# hybrid.net
KiCad netlist of a schematic drawn in EAGLE
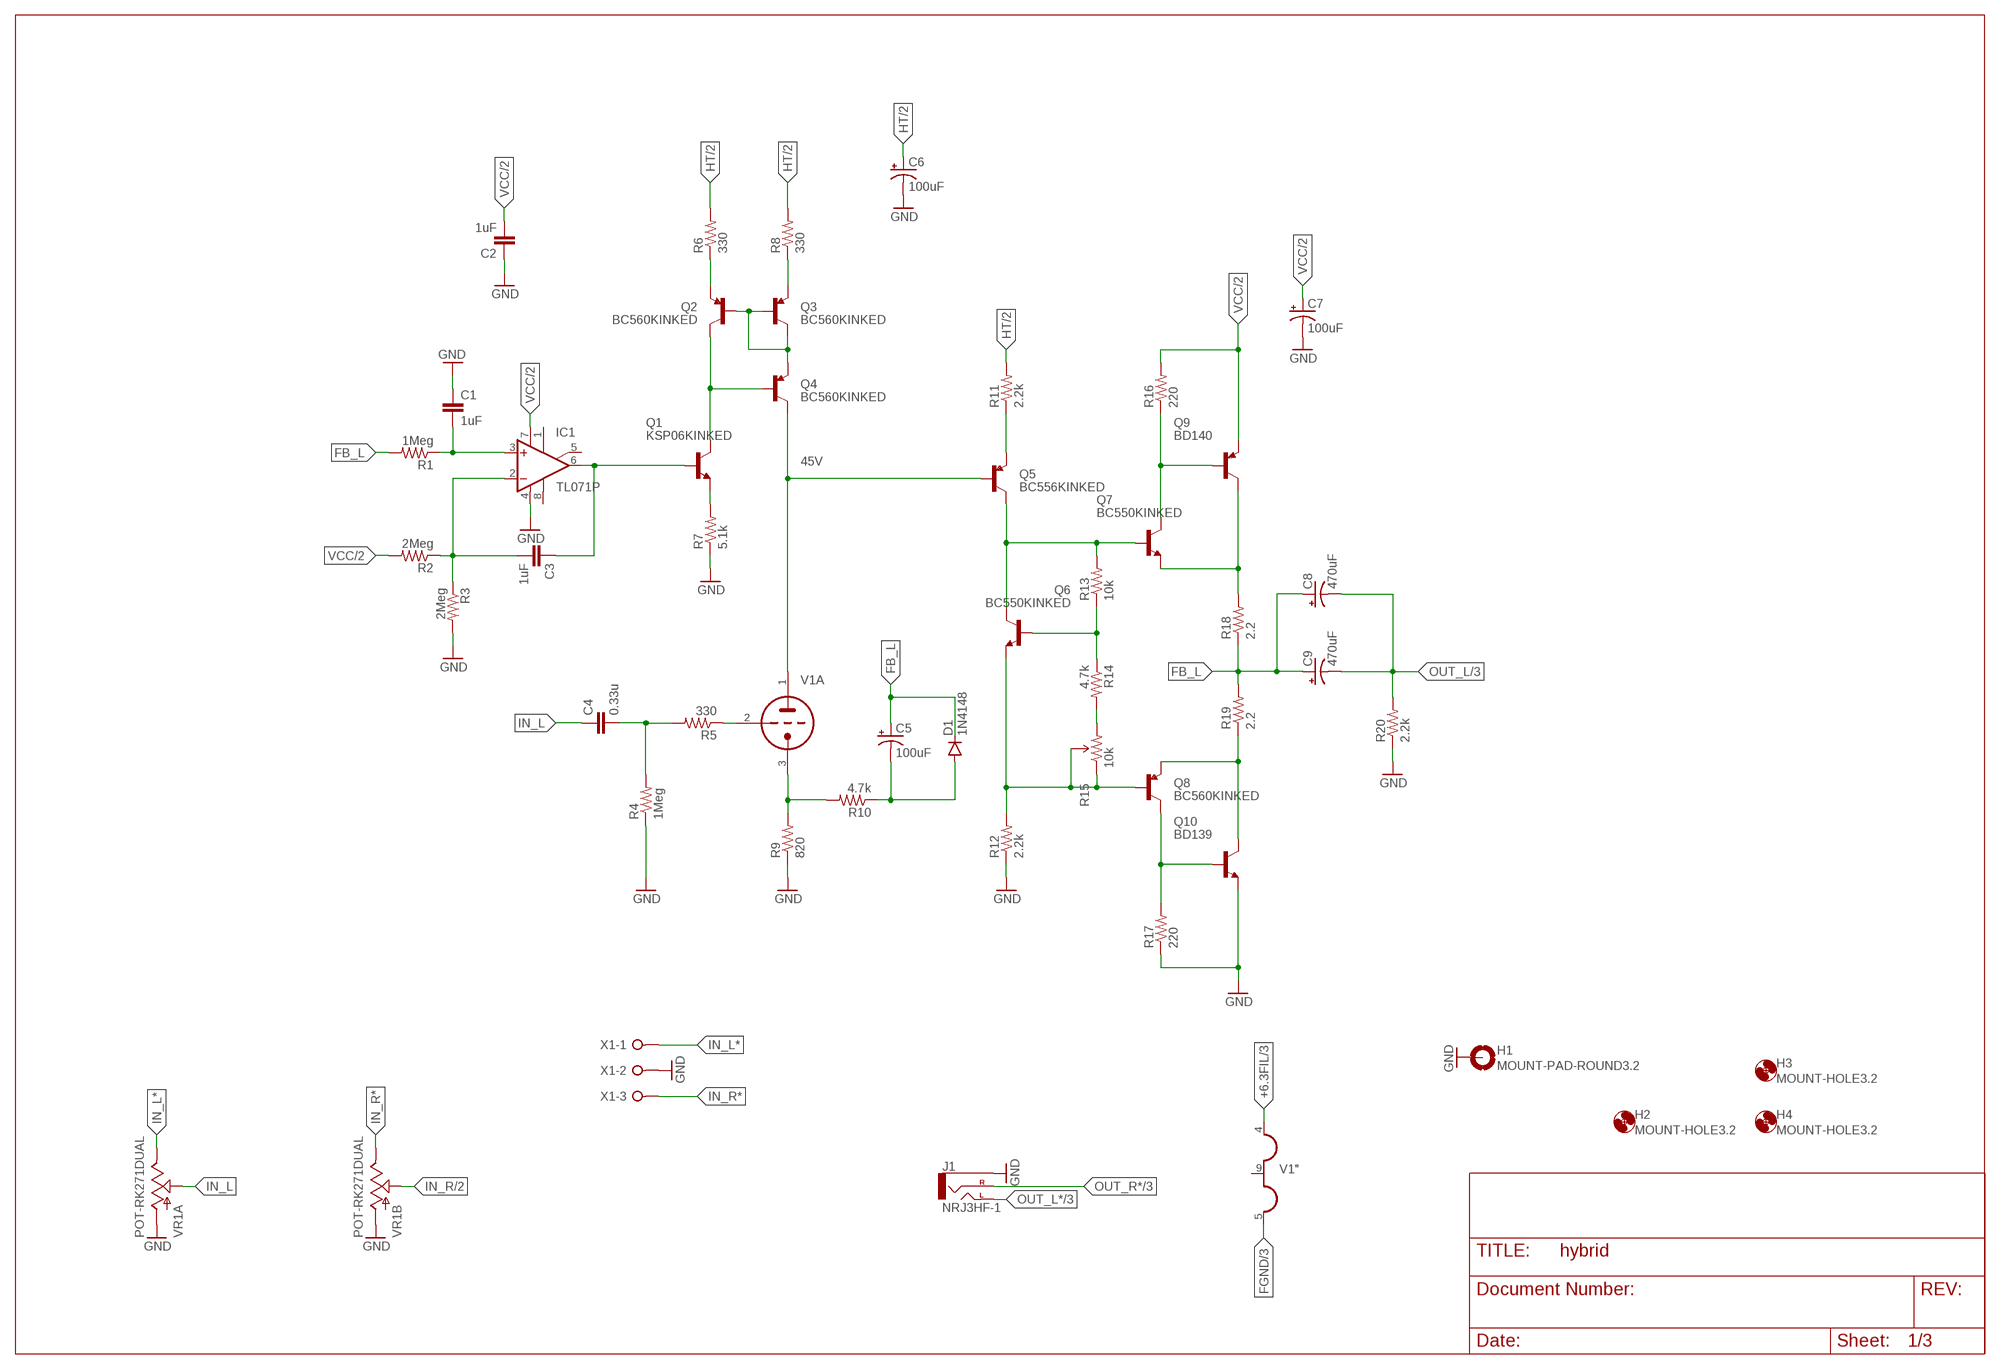
[diagram p0: schematic, sheet 1]
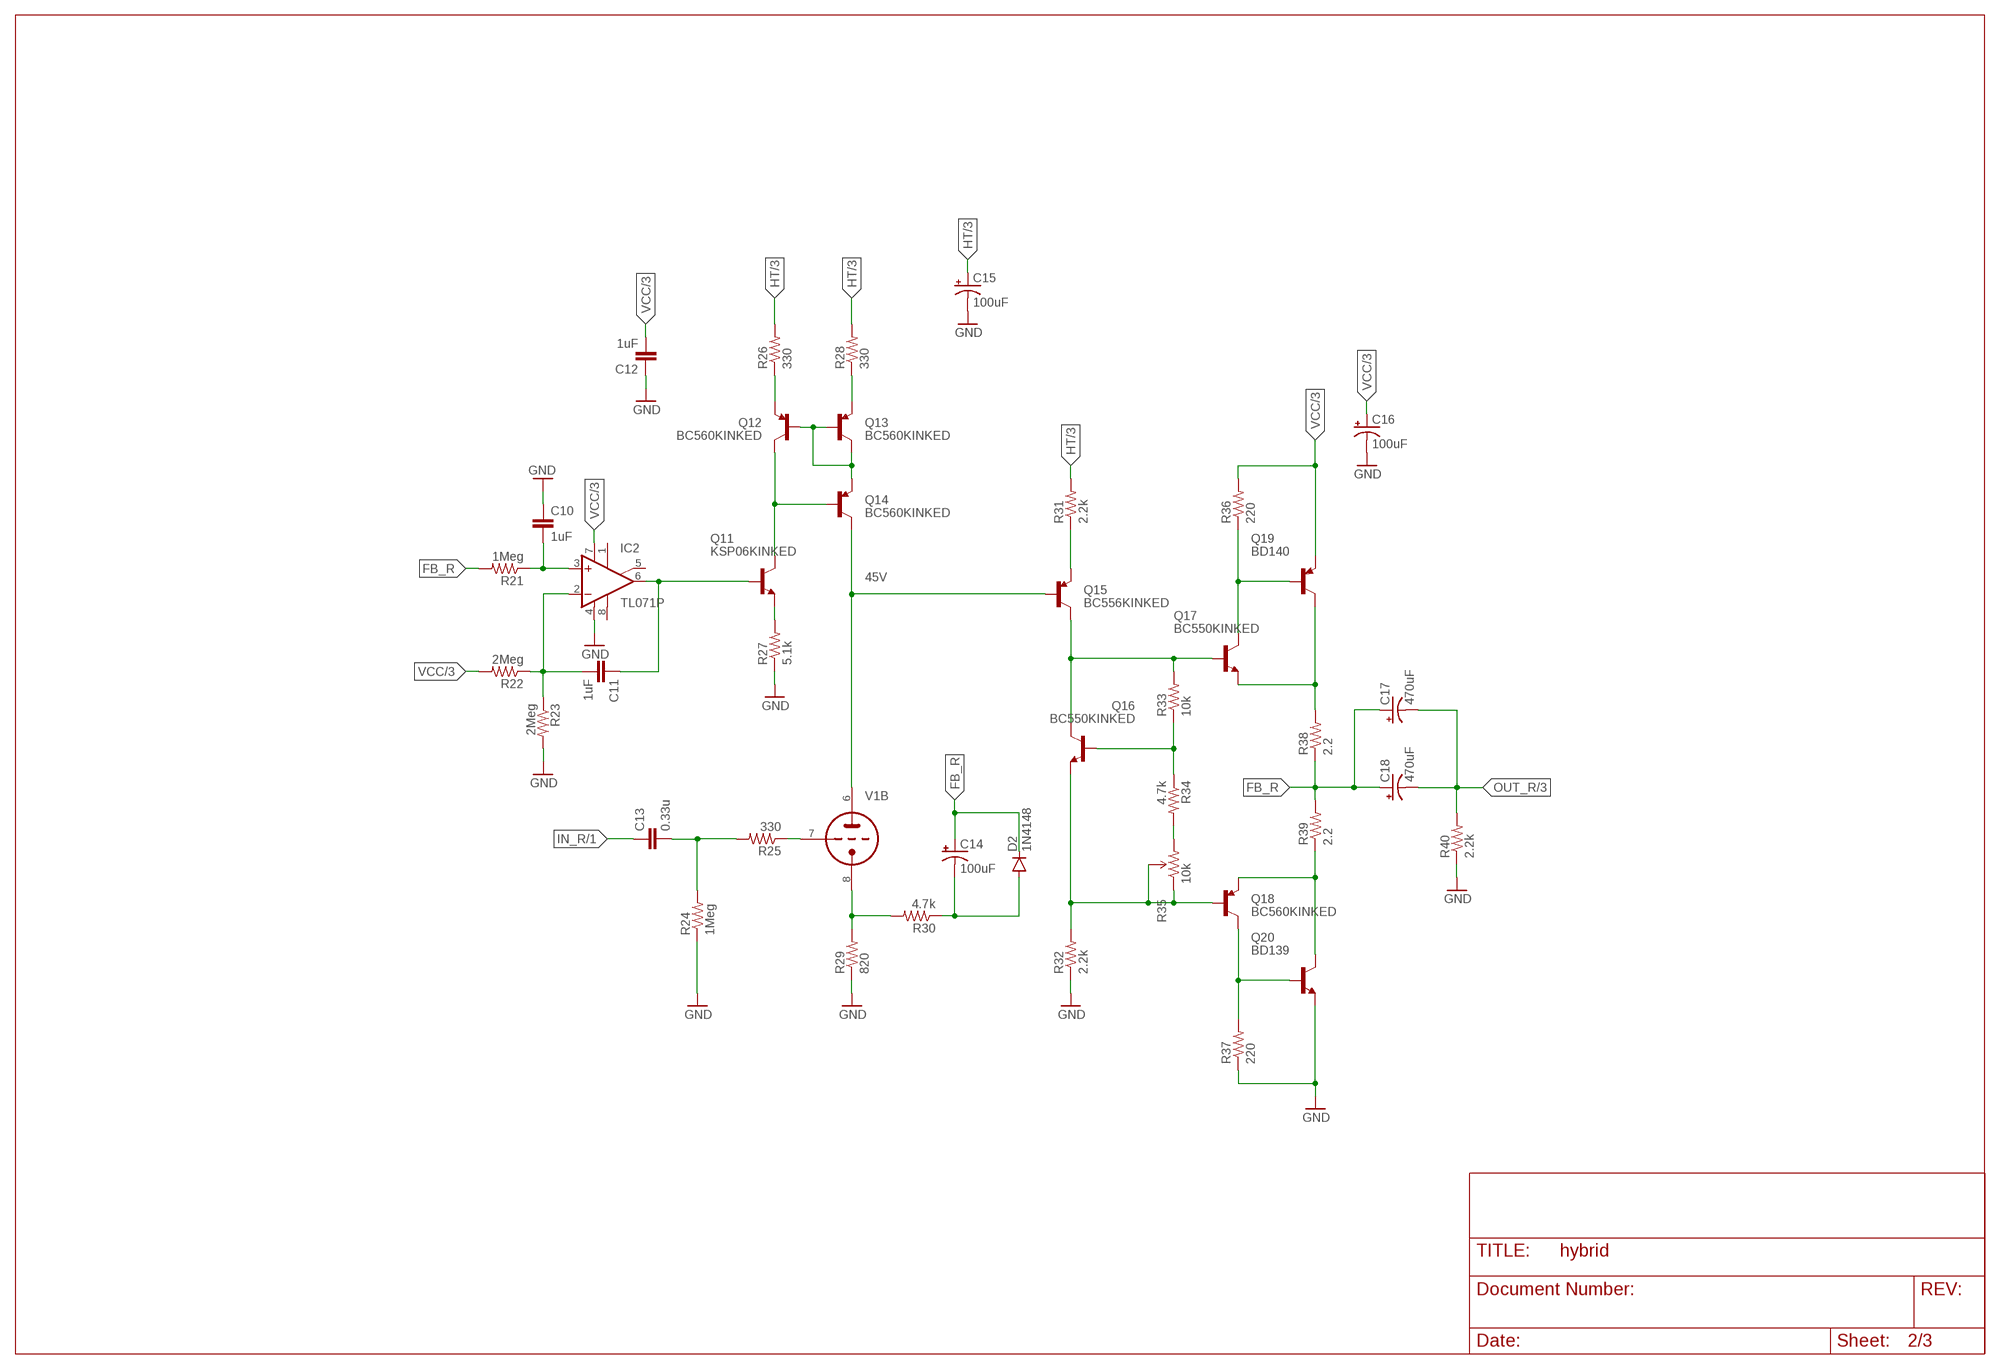
[diagram p1: schematic, sheet 2]
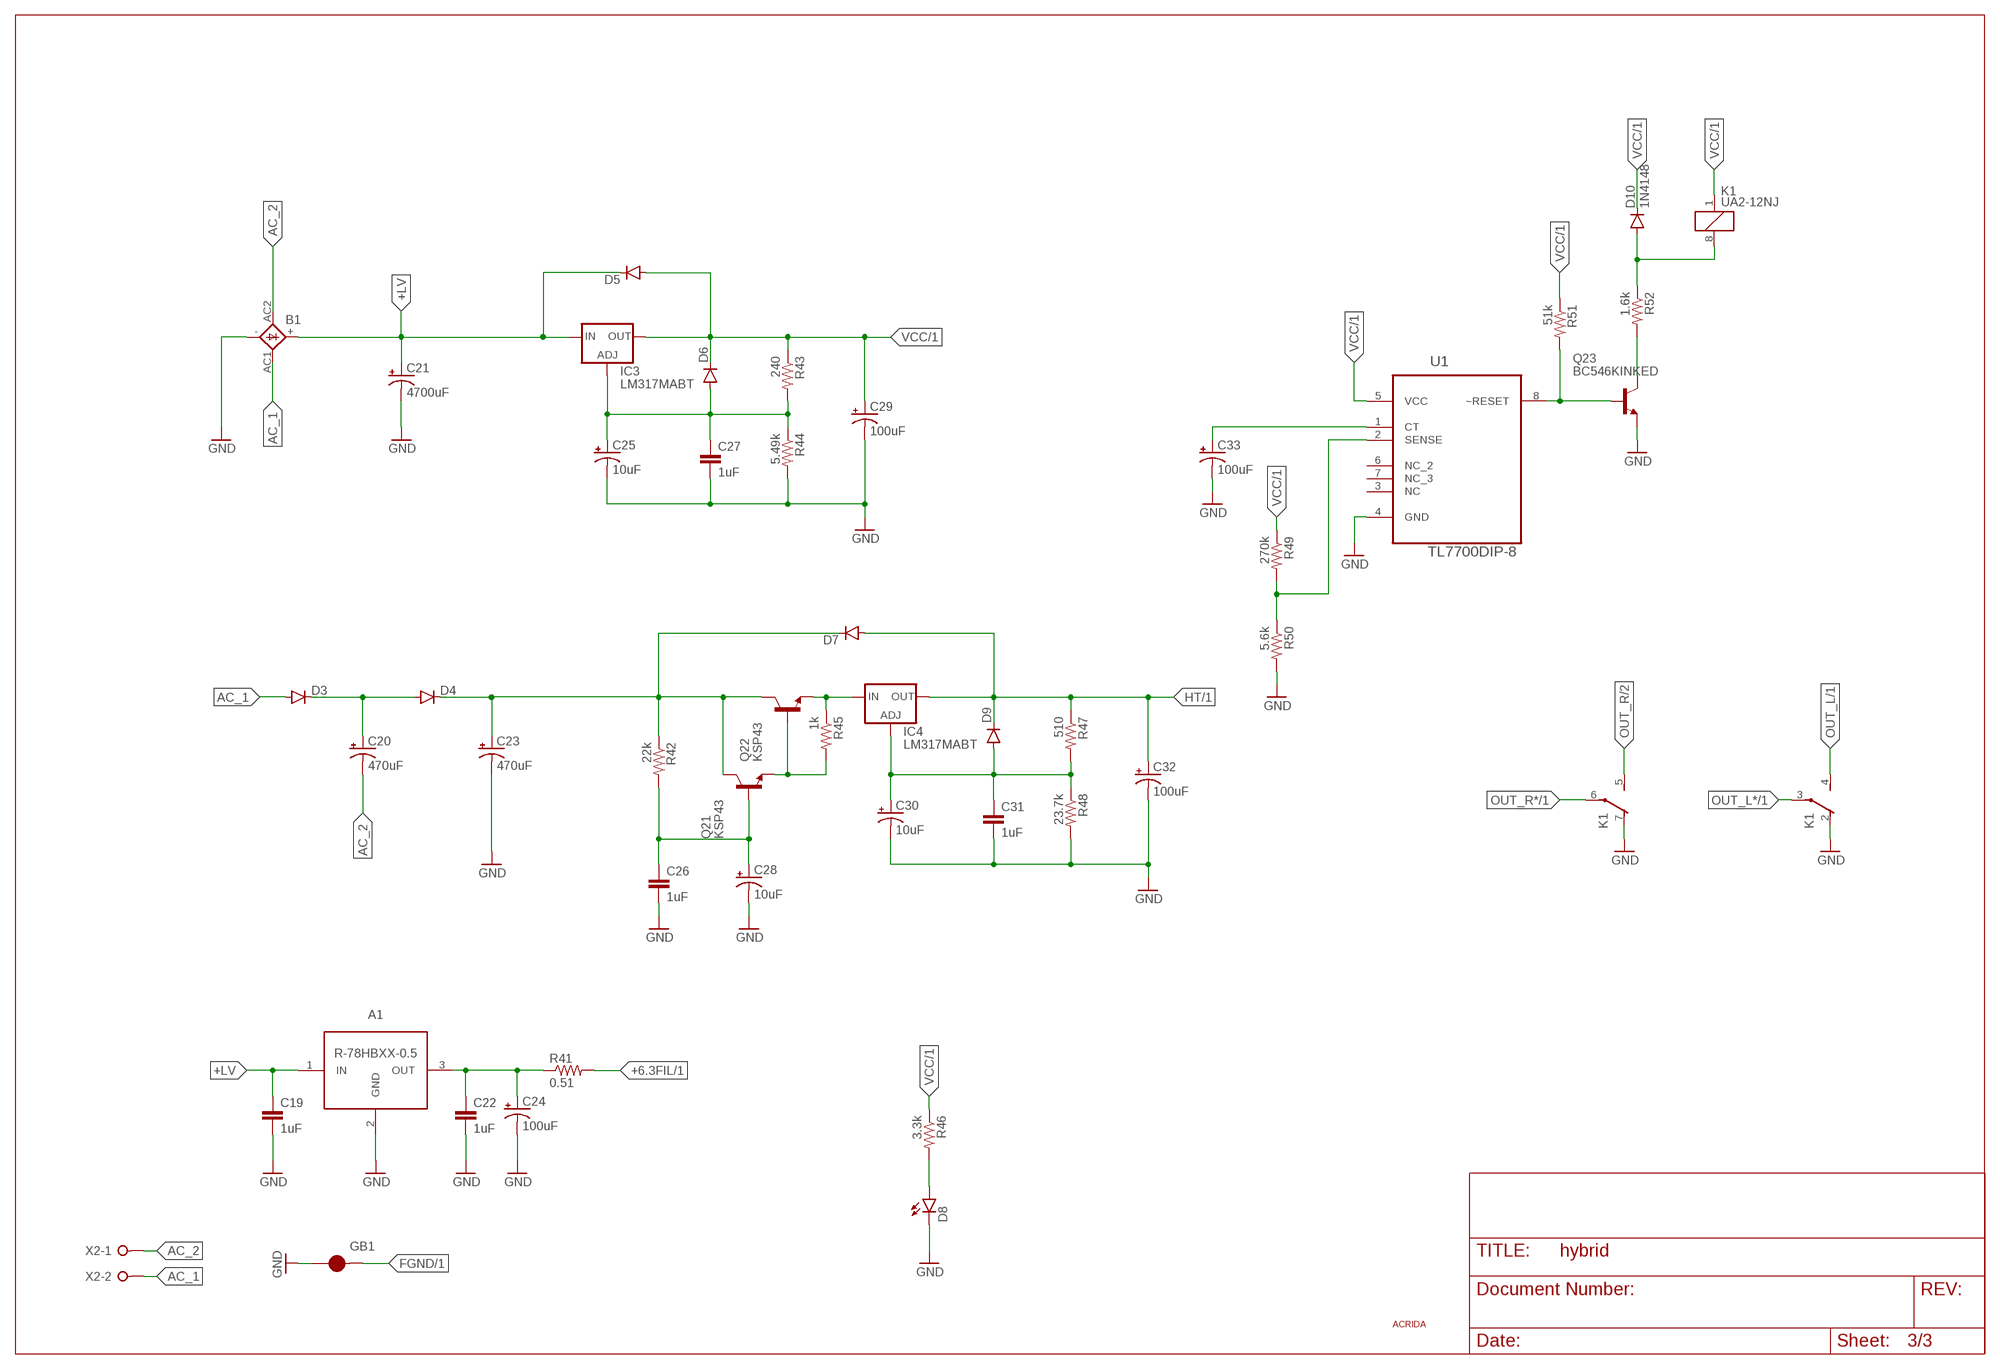
[diagram p2: schematic, sheet 3]

(export (version "E")
  (design (tool "Eeschema 10.0.6"))
  (components
    (comp (ref "A1")
      (value "R-78HBXX-0.5")
      (footprint "eagle-import:R-78HB")
      (libsource (lib "eagle-import") (part "R-78HBXX-0.5"))
    )
    (comp (ref "B1")
      (value "GBU4")
      (footprint "eagle-import:GBU4S")
      (libsource (lib "eagle-import") (part "GBU4"))
    )
    (comp (ref "C19")
      (value "1uF")
      (footprint "eagle-import:CAP-PTH-5MM")
      (libsource (lib "eagle-import") (part "CAPPTH1"))
    )
    (comp (ref "C20")
      (value "470uF")
      (footprint "eagle-import:CPOL-SNAPIN-22_10")
      (libsource (lib "eagle-import") (part "CAP_POLSNAPIN-22/10"))
    )
    (comp (ref "C21")
      (value "4700uF")
      (footprint "eagle-import:CPOL-SNAPIN-30_10")
      (libsource (lib "eagle-import") (part "CAP_POLSNAPIN-30/10"))
    )
    (comp (ref "C22")
      (value "1uF")
      (footprint "eagle-import:CAP-PTH-SMALL")
      (libsource (lib "eagle-import") (part "CAPPTH"))
    )
    (comp (ref "C23")
      (value "470uF")
      (footprint "eagle-import:CPOL-SNAPIN-22_10")
      (libsource (lib "eagle-import") (part "CAP_POLSNAPIN-22/10"))
    )
    (comp (ref "C24")
      (value "100uF")
      (footprint "eagle-import:CPOL-RADIAL-6.5_2.5")
      (libsource (lib "eagle-import") (part "CAP_POLPTH-6.5/2.5"))
    )
    (comp (ref "C25")
      (value "10uF")
      (footprint "eagle-import:CPOL-RADIAL-6.5_2.5")
      (libsource (lib "eagle-import") (part "CAP_POLPTH-6.5/2.5"))
    )
    (comp (ref "C26")
      (value "1uF")
      (footprint "eagle-import:CAP-PTH-5MM")
      (libsource (lib "eagle-import") (part "CAPPTH1"))
    )
    (comp (ref "C27")
      (value "1uF")
      (footprint "eagle-import:CAP-PTH-SMALL")
      (libsource (lib "eagle-import") (part "CAPPTH"))
    )
    (comp (ref "C28")
      (value "10uF")
      (footprint "eagle-import:CPOL-RADIAL-12_5")
      (libsource (lib "eagle-import") (part "CAP_POLPTH-12/5"))
    )
    (comp (ref "C29")
      (value "100uF")
      (footprint "eagle-import:CPOL-RADIAL-12.5_5")
      (libsource (lib "eagle-import") (part "CAP_POLPTH-12.5/5"))
    )
    (comp (ref "C30")
      (value "10uF")
      (footprint "eagle-import:CPOL-RADIAL-6.5_2.5")
      (libsource (lib "eagle-import") (part "CAP_POLPTH-6.5/2.5"))
    )
    (comp (ref "C31")
      (value "1uF")
      (footprint "eagle-import:CAP-PTH-SMALL")
      (libsource (lib "eagle-import") (part "CAPPTH"))
    )
    (comp (ref "C32")
      (value "100uF")
      (footprint "eagle-import:CPOL-RADIAL-12.5_5")
      (libsource (lib "eagle-import") (part "CAP_POLPTH-12.5/5"))
    )
    (comp (ref "C33")
      (value "100uF")
      (footprint "eagle-import:CPOL-RADIAL-6.5_2.5")
      (libsource (lib "eagle-import") (part "CAP_POLPTH-6.5/2.5"))
    )
    (comp (ref "D3")
      (value "DIODEPTH")
      (footprint "eagle-import:DIODE-1N4001")
      (libsource (lib "eagle-import") (part "DIODEPTH"))
    )
    (comp (ref "D4")
      (value "DIODEPTH")
      (footprint "eagle-import:DIODE-1N4001")
      (libsource (lib "eagle-import") (part "DIODEPTH"))
    )
    (comp (ref "D5")
      (value "DIODEPTH")
      (footprint "eagle-import:DIODE-1N4001")
      (libsource (lib "eagle-import") (part "DIODEPTH"))
    )
    (comp (ref "D6")
      (value "DIODEPTH")
      (footprint "eagle-import:DIODE-1N4001")
      (libsource (lib "eagle-import") (part "DIODEPTH"))
    )
    (comp (ref "D7")
      (value "DIODEPTH")
      (footprint "eagle-import:DIODE-1N4001")
      (libsource (lib "eagle-import") (part "DIODEPTH"))
    )
    (comp (ref "D8")
      (value "LED3MM")
      (footprint "eagle-import:LED3MM")
      (libsource (lib "eagle-import") (part "LED3MM"))
    )
    (comp (ref "D9")
      (value "DIODEPTH")
      (footprint "eagle-import:DIODE-1N4001")
      (libsource (lib "eagle-import") (part "DIODEPTH"))
    )
    (comp (ref "D10")
      (value "1N4148")
      (footprint "eagle-import:DIODE-1N4148")
      (libsource (lib "eagle-import") (part "my_DIODE1N4148"))
    )
    (comp (ref "GB1")
      (value "COPPER-BRIDGESM")
      (footprint "eagle-import:COPPER-BRIDGE-SM")
      (libsource (lib "eagle-import") (part "COPPER-BRIDGESM"))
    )
    (comp (ref "IC3")
      (value "LM317MABT")
      (footprint "eagle-import:TO220L1")
      (libsource (lib "eagle-import") (part "LM317?MABT"))
    )
    (comp (ref "IC4")
      (value "LM317MABT")
      (footprint "eagle-import:TO220L1")
      (libsource (lib "eagle-import") (part "LM317?MABT"))
    )
    (comp (ref "K1")
      (value "UA2-12NJ")
      (footprint "eagle-import:UA2")
      (libsource (lib "eagle-import") (part "UA2-12NJ"))
    )
    (comp (ref "LOGO1")
      (value "ACRIDA-LOGO")
      (footprint "eagle-import:ACRIDA-LOGO")
      (libsource (lib "eagle-import") (part "ACRIDA-LOGO"))
    )
    (comp (ref "Q21")
      (value "KSP43")
      (footprint "eagle-import:TO-92")
      (libsource (lib "eagle-import") (part "KSP43"))
    )
    (comp (ref "Q22")
      (value "KSP43")
      (footprint "eagle-import:TO-92")
      (libsource (lib "eagle-import") (part "KSP43"))
    )
    (comp (ref "Q23")
      (value "BC546KINKED")
      (footprint "eagle-import:TO92-BENT")
      (libsource (lib "eagle-import") (part "BC546KINKED"))
    )
    (comp (ref "R41")
      (value "0.51")
      (footprint "eagle-import:AXIAL-0.5")
      (libsource (lib "eagle-import") (part "my-res_RESISTORPTH-1/2W"))
    )
    (comp (ref "R42")
      (value "22k")
      (footprint "eagle-import:AXIAL-0.4")
      (libsource (lib "eagle-import") (part "RESISTORPTH-1/4W"))
    )
    (comp (ref "R43")
      (value "240")
      (footprint "eagle-import:AXIAL-0.4")
      (libsource (lib "eagle-import") (part "RESISTORPTH-1/4W"))
    )
    (comp (ref "R44")
      (value "5.49k")
      (footprint "eagle-import:AXIAL-0.4")
      (libsource (lib "eagle-import") (part "RESISTORPTH-1/4W"))
    )
    (comp (ref "R45")
      (value "1k")
      (footprint "eagle-import:AXIAL-0.4")
      (libsource (lib "eagle-import") (part "RESISTORPTH-1/4W"))
    )
    (comp (ref "R46")
      (value "3.3k")
      (footprint "eagle-import:AXIAL-0.4")
      (libsource (lib "eagle-import") (part "RESISTORPTH-1/4W"))
    )
    (comp (ref "R47")
      (value "510")
      (footprint "eagle-import:AXIAL-0.4")
      (libsource (lib "eagle-import") (part "RESISTORPTH-1/4W"))
    )
    (comp (ref "R48")
      (value "23.7k")
      (footprint "eagle-import:AXIAL-0.4")
      (libsource (lib "eagle-import") (part "RESISTORPTH-1/4W"))
    )
    (comp (ref "R49")
      (value "270k")
      (footprint "eagle-import:AXIAL-0.4")
      (libsource (lib "eagle-import") (part "RESISTORPTH-1/4W"))
    )
    (comp (ref "R50")
      (value "5.6k")
      (footprint "eagle-import:AXIAL-0.4")
      (libsource (lib "eagle-import") (part "RESISTORPTH-1/4W"))
    )
    (comp (ref "R51")
      (value "51k")
      (footprint "eagle-import:AXIAL-0.4")
      (libsource (lib "eagle-import") (part "RESISTORPTH-1/4W"))
    )
    (comp (ref "R52")
      (value "1.6k")
      (footprint "eagle-import:AXIAL-0.4")
      (libsource (lib "eagle-import") (part "RESISTORPTH-1/4W"))
    )
    (comp (ref "U1")
      (value "TL7700DIP-8")
      (footprint "eagle-import:DIL08")
      (libsource (lib "eagle-import") (part "TL7700DIP-8"))
    )
    (comp (ref "X2")
      (value "W237-2N")
      (footprint "eagle-import:W237-2N")
      (libsource (lib "eagle-import") (part "W237-2N"))
    )
    (comp (ref "C10")
      (value "1uF")
      (footprint "eagle-import:C5B5")
      (libsource (lib "eagle-import") (part "C5/5"))
    )
    (comp (ref "C11")
      (value "1uF")
      (footprint "eagle-import:C5B5")
      (libsource (lib "eagle-import") (part "C5/5"))
    )
    (comp (ref "C12")
      (value "1uF")
      (footprint "eagle-import:CAP-PTH-SMALL")
      (libsource (lib "eagle-import") (part "CAPPTH"))
    )
    (comp (ref "C13")
      (value "0.33u")
      (footprint "eagle-import:C5B7.2")
      (libsource (lib "eagle-import") (part "C5/7.2"))
    )
    (comp (ref "C14")
      (value "100uF")
      (footprint "eagle-import:CPOL-RADIAL-8_3.5")
      (libsource (lib "eagle-import") (part "CAP_POLPTH-8/3.5"))
    )
    (comp (ref "C15")
      (value "100uF")
      (footprint "eagle-import:CPOL-RADIAL-12.5_5")
      (libsource (lib "eagle-import") (part "CAP_POLPTH-12.5/5"))
    )
    (comp (ref "C16")
      (value "100uF")
      (footprint "eagle-import:CPOL-RADIAL-12.5_5")
      (libsource (lib "eagle-import") (part "CAP_POLPTH-12.5/5"))
    )
    (comp (ref "C17")
      (value "470uF")
      (footprint "eagle-import:CPOL-RADIAL-12.5_5")
      (libsource (lib "eagle-import") (part "CAP_POLPTH-12.5/5"))
    )
    (comp (ref "C18")
      (value "470uF")
      (footprint "eagle-import:CPOL-RADIAL-12.5_5")
      (libsource (lib "eagle-import") (part "CAP_POLPTH-12.5/5"))
    )
    (comp (ref "D2")
      (value "1N4148")
      (footprint "eagle-import:DIODE-1N4148")
      (libsource (lib "eagle-import") (part "my_DIODE1N4148"))
    )
    (comp (ref "IC2")
      (value "TL071P")
      (footprint "eagle-import:DIL08")
      (libsource (lib "eagle-import") (part "TL071P"))
    )
    (comp (ref "Q11")
      (value "KSP06KINKED")
      (footprint "eagle-import:TO92-BENT")
      (libsource (lib "eagle-import") (part "KSP06KINKED"))
    )
    (comp (ref "Q12")
      (value "BC560KINKED")
      (footprint "eagle-import:TO92-BENT")
      (libsource (lib "eagle-import") (part "BC560KINKED"))
    )
    (comp (ref "Q13")
      (value "BC560KINKED")
      (footprint "eagle-import:TO92-BENT")
      (libsource (lib "eagle-import") (part "BC560KINKED"))
    )
    (comp (ref "Q14")
      (value "BC560KINKED")
      (footprint "eagle-import:TO92-BENT")
      (libsource (lib "eagle-import") (part "BC560KINKED"))
    )
    (comp (ref "Q15")
      (value "BC556KINKED")
      (footprint "eagle-import:TO92-BENT")
      (libsource (lib "eagle-import") (part "BC556KINKED"))
    )
    (comp (ref "Q16")
      (value "BC550KINKED")
      (footprint "eagle-import:TO92-BENT")
      (libsource (lib "eagle-import") (part "BC550KINKED"))
    )
    (comp (ref "Q17")
      (value "BC550KINKED")
      (footprint "eagle-import:TO92-BENT")
      (libsource (lib "eagle-import") (part "BC550KINKED"))
    )
    (comp (ref "Q18")
      (value "BC560KINKED")
      (footprint "eagle-import:TO92-BENT")
      (libsource (lib "eagle-import") (part "BC560KINKED"))
    )
    (comp (ref "Q19")
      (value "BD140")
      (footprint "eagle-import:TO126")
      (libsource (lib "eagle-import") (part "BD140"))
    )
    (comp (ref "Q20")
      (value "BD139")
      (footprint "eagle-import:TO126")
      (libsource (lib "eagle-import") (part "BD139"))
    )
    (comp (ref "R21")
      (value "1Meg")
      (footprint "eagle-import:AXIAL-0.4")
      (libsource (lib "eagle-import") (part "RESISTORPTH-1/4W"))
    )
    (comp (ref "R22")
      (value "2Meg")
      (footprint "eagle-import:AXIAL-0.4")
      (libsource (lib "eagle-import") (part "RESISTORPTH-1/4W"))
    )
    (comp (ref "R23")
      (value "2Meg")
      (footprint "eagle-import:AXIAL-0.4")
      (libsource (lib "eagle-import") (part "RESISTORPTH-1/4W"))
    )
    (comp (ref "R24")
      (value "1Meg")
      (footprint "eagle-import:AXIAL-0.4")
      (libsource (lib "eagle-import") (part "RESISTORPTH-1/4W"))
    )
    (comp (ref "R25")
      (value "330")
      (footprint "eagle-import:AXIAL-0.4")
      (libsource (lib "eagle-import") (part "RESISTORPTH-1/4W"))
    )
    (comp (ref "R26")
      (value "330")
      (footprint "eagle-import:AXIAL-0.4")
      (libsource (lib "eagle-import") (part "RESISTORPTH-1/4W"))
    )
    (comp (ref "R27")
      (value "5.1k")
      (footprint "eagle-import:AXIAL-0.4")
      (libsource (lib "eagle-import") (part "RESISTORPTH-1/4W"))
    )
    (comp (ref "R28")
      (value "330")
      (footprint "eagle-import:AXIAL-0.4")
      (libsource (lib "eagle-import") (part "RESISTORPTH-1/4W"))
    )
    (comp (ref "R29")
      (value "820")
      (footprint "eagle-import:AXIAL-0.4")
      (libsource (lib "eagle-import") (part "RESISTORPTH-1/4W"))
    )
    (comp (ref "R30")
      (value "4.7k")
      (footprint "eagle-import:AXIAL-0.4")
      (libsource (lib "eagle-import") (part "RESISTORPTH-1/4W"))
    )
    (comp (ref "R31")
      (value "2.2k")
      (footprint "eagle-import:AXIAL-0.4")
      (libsource (lib "eagle-import") (part "RESISTORPTH-1/4W"))
    )
    (comp (ref "R32")
      (value "2.2k")
      (footprint "eagle-import:AXIAL-0.4")
      (libsource (lib "eagle-import") (part "RESISTORPTH-1/4W"))
    )
    (comp (ref "R33")
      (value "10k")
      (footprint "eagle-import:AXIAL-0.4")
      (libsource (lib "eagle-import") (part "RESISTORPTH-1/4W"))
    )
    (comp (ref "R34")
      (value "4.7k")
      (footprint "eagle-import:AXIAL-0.4")
      (libsource (lib "eagle-import") (part "RESISTORPTH-1/4W"))
    )
    (comp (ref "R35")
      (value "10k")
      (footprint "eagle-import:3362U-2")
      (libsource (lib "eagle-import") (part "TRIMPOT3362U-2"))
    )
    (comp (ref "R36")
      (value "220")
      (footprint "eagle-import:AXIAL-0.4")
      (libsource (lib "eagle-import") (part "RESISTORPTH-1/4W"))
    )
    (comp (ref "R37")
      (value "220")
      (footprint "eagle-import:AXIAL-0.4")
      (libsource (lib "eagle-import") (part "RESISTORPTH-1/4W"))
    )
    (comp (ref "R38")
      (value "2.2")
      (footprint "eagle-import:AXIAL-0.4")
      (libsource (lib "eagle-import") (part "RESISTORPTH-1/4W"))
    )
    (comp (ref "R39")
      (value "2.2")
      (footprint "eagle-import:AXIAL-0.4")
      (libsource (lib "eagle-import") (part "RESISTORPTH-1/4W"))
    )
    (comp (ref "R40")
      (value "2.2k")
      (footprint "eagle-import:AXIAL-0.4")
      (libsource (lib "eagle-import") (part "RESISTORPTH-1/4W"))
    )
    (comp (ref "V1")
      (value "6DJ8-P21MM-BASE")
      (footprint "eagle-import:NOVAL-21MM")
      (libsource (lib "eagle-import") (part "6DJ8-P21MM-BASE"))
    )
    (comp (ref "C1")
      (value "1uF")
      (footprint "eagle-import:C5B5")
      (libsource (lib "eagle-import") (part "C5/5"))
    )
    (comp (ref "C2")
      (value "1uF")
      (footprint "eagle-import:CAP-PTH-SMALL")
      (libsource (lib "eagle-import") (part "CAPPTH"))
    )
    (comp (ref "C3")
      (value "1uF")
      (footprint "eagle-import:C5B5")
      (libsource (lib "eagle-import") (part "C5/5"))
    )
    (comp (ref "C4")
      (value "0.33u")
      (footprint "eagle-import:C5B7.2")
      (libsource (lib "eagle-import") (part "C5/7.2"))
    )
    (comp (ref "C5")
      (value "100uF")
      (footprint "eagle-import:CPOL-RADIAL-8_3.5")
      (libsource (lib "eagle-import") (part "CAP_POLPTH-8/3.5"))
    )
    (comp (ref "C6")
      (value "100uF")
      (footprint "eagle-import:CPOL-RADIAL-12.5_5")
      (libsource (lib "eagle-import") (part "CAP_POLPTH-12.5/5"))
    )
    (comp (ref "C7")
      (value "100uF")
      (footprint "eagle-import:CPOL-RADIAL-12.5_5")
      (libsource (lib "eagle-import") (part "CAP_POLPTH-12.5/5"))
    )
    (comp (ref "C8")
      (value "470uF")
      (footprint "eagle-import:CPOL-RADIAL-12.5_5")
      (libsource (lib "eagle-import") (part "CAP_POLPTH-12.5/5"))
    )
    (comp (ref "C9")
      (value "470uF")
      (footprint "eagle-import:CPOL-RADIAL-12.5_5")
      (libsource (lib "eagle-import") (part "CAP_POLPTH-12.5/5"))
    )
    (comp (ref "D1")
      (value "1N4148")
      (footprint "eagle-import:DIODE-1N4148")
      (libsource (lib "eagle-import") (part "my_DIODE1N4148"))
    )
    (comp (ref "H1")
      (value "MOUNT-PAD-ROUND3.2")
      (footprint "eagle-import:3,2-PAD")
      (libsource (lib "eagle-import") (part "MOUNT-PAD-ROUND3.2"))
    )
    (comp (ref "H2")
      (value "MOUNT-HOLE3.2")
      (footprint "eagle-import:3,2")
      (libsource (lib "eagle-import") (part "MOUNT-HOLE3.2"))
    )
    (comp (ref "H3")
      (value "MOUNT-HOLE3.2")
      (footprint "eagle-import:3,2")
      (libsource (lib "eagle-import") (part "MOUNT-HOLE3.2"))
    )
    (comp (ref "H4")
      (value "MOUNT-HOLE3.2")
      (footprint "eagle-import:3,2")
      (libsource (lib "eagle-import") (part "MOUNT-HOLE3.2"))
    )
    (comp (ref "IC1")
      (value "TL071P")
      (footprint "eagle-import:DIL08")
      (libsource (lib "eagle-import") (part "TL071P"))
    )
    (comp (ref "J1")
      (value "NRJ3HF-1")
      (footprint "eagle-import:NRJ3HF")
      (libsource (lib "eagle-import") (part "NRJ3HF-1"))
    )
    (comp (ref "Q1")
      (value "KSP06KINKED")
      (footprint "eagle-import:TO92-BENT")
      (libsource (lib "eagle-import") (part "KSP06KINKED"))
    )
    (comp (ref "Q2")
      (value "BC560KINKED")
      (footprint "eagle-import:TO92-BENT")
      (libsource (lib "eagle-import") (part "BC560KINKED"))
    )
    (comp (ref "Q3")
      (value "BC560KINKED")
      (footprint "eagle-import:TO92-BENT")
      (libsource (lib "eagle-import") (part "BC560KINKED"))
    )
    (comp (ref "Q4")
      (value "BC560KINKED")
      (footprint "eagle-import:TO92-BENT")
      (libsource (lib "eagle-import") (part "BC560KINKED"))
    )
    (comp (ref "Q5")
      (value "BC556KINKED")
      (footprint "eagle-import:TO92-BENT")
      (libsource (lib "eagle-import") (part "BC556KINKED"))
    )
    (comp (ref "Q6")
      (value "BC550KINKED")
      (footprint "eagle-import:TO92-BENT")
      (libsource (lib "eagle-import") (part "BC550KINKED"))
    )
    (comp (ref "Q7")
      (value "BC550KINKED")
      (footprint "eagle-import:TO92-BENT")
      (libsource (lib "eagle-import") (part "BC550KINKED"))
    )
    (comp (ref "Q8")
      (value "BC560KINKED")
      (footprint "eagle-import:TO92-BENT")
      (libsource (lib "eagle-import") (part "BC560KINKED"))
    )
    (comp (ref "Q9")
      (value "BD140")
      (footprint "eagle-import:TO126")
      (libsource (lib "eagle-import") (part "BD140"))
    )
    (comp (ref "Q10")
      (value "BD139")
      (footprint "eagle-import:TO126")
      (libsource (lib "eagle-import") (part "BD139"))
    )
    (comp (ref "R1")
      (value "1Meg")
      (footprint "eagle-import:AXIAL-0.4")
      (libsource (lib "eagle-import") (part "RESISTORPTH-1/4W"))
    )
    (comp (ref "R2")
      (value "2Meg")
      (footprint "eagle-import:AXIAL-0.4")
      (libsource (lib "eagle-import") (part "RESISTORPTH-1/4W"))
    )
    (comp (ref "R3")
      (value "2Meg")
      (footprint "eagle-import:AXIAL-0.4")
      (libsource (lib "eagle-import") (part "RESISTORPTH-1/4W"))
    )
    (comp (ref "R4")
      (value "1Meg")
      (footprint "eagle-import:AXIAL-0.4")
      (libsource (lib "eagle-import") (part "RESISTORPTH-1/4W"))
    )
    (comp (ref "R5")
      (value "330")
      (footprint "eagle-import:AXIAL-0.4")
      (libsource (lib "eagle-import") (part "RESISTORPTH-1/4W"))
    )
    (comp (ref "R6")
      (value "330")
      (footprint "eagle-import:AXIAL-0.4")
      (libsource (lib "eagle-import") (part "RESISTORPTH-1/4W"))
    )
    (comp (ref "R7")
      (value "5.1k")
      (footprint "eagle-import:AXIAL-0.4")
      (libsource (lib "eagle-import") (part "RESISTORPTH-1/4W"))
    )
    (comp (ref "R8")
      (value "330")
      (footprint "eagle-import:AXIAL-0.4")
      (libsource (lib "eagle-import") (part "RESISTORPTH-1/4W"))
    )
    (comp (ref "R9")
      (value "820")
      (footprint "eagle-import:AXIAL-0.4")
      (libsource (lib "eagle-import") (part "RESISTORPTH-1/4W"))
    )
    (comp (ref "R10")
      (value "4.7k")
      (footprint "eagle-import:AXIAL-0.4")
      (libsource (lib "eagle-import") (part "RESISTORPTH-1/4W"))
    )
    (comp (ref "R11")
      (value "2.2k")
      (footprint "eagle-import:AXIAL-0.4")
      (libsource (lib "eagle-import") (part "RESISTORPTH-1/4W"))
    )
    (comp (ref "R12")
      (value "2.2k")
      (footprint "eagle-import:AXIAL-0.4")
      (libsource (lib "eagle-import") (part "RESISTORPTH-1/4W"))
    )
    (comp (ref "R13")
      (value "10k")
      (footprint "eagle-import:AXIAL-0.4")
      (libsource (lib "eagle-import") (part "RESISTORPTH-1/4W"))
    )
    (comp (ref "R14")
      (value "4.7k")
      (footprint "eagle-import:AXIAL-0.4")
      (libsource (lib "eagle-import") (part "RESISTORPTH-1/4W"))
    )
    (comp (ref "R15")
      (value "10k")
      (footprint "eagle-import:3362U-2")
      (libsource (lib "eagle-import") (part "TRIMPOT3362U-2"))
    )
    (comp (ref "R16")
      (value "220")
      (footprint "eagle-import:AXIAL-0.4")
      (libsource (lib "eagle-import") (part "RESISTORPTH-1/4W"))
    )
    (comp (ref "R17")
      (value "220")
      (footprint "eagle-import:AXIAL-0.4")
      (libsource (lib "eagle-import") (part "RESISTORPTH-1/4W"))
    )
    (comp (ref "R18")
      (value "2.2")
      (footprint "eagle-import:AXIAL-0.4")
      (libsource (lib "eagle-import") (part "RESISTORPTH-1/4W"))
    )
    (comp (ref "R19")
      (value "2.2")
      (footprint "eagle-import:AXIAL-0.4")
      (libsource (lib "eagle-import") (part "RESISTORPTH-1/4W"))
    )
    (comp (ref "R20")
      (value "2.2k")
      (footprint "eagle-import:AXIAL-0.4")
      (libsource (lib "eagle-import") (part "RESISTORPTH-1/4W"))
    )
    (comp (ref "VR1")
      (value "POT-RK271DUAL")
      (footprint "eagle-import:RK271+PTD902")
      (libsource (lib "eagle-import") (part "POT-RK271DUAL"))
    )
    (comp (ref "X1")
      (value "W237-3E")
      (footprint "eagle-import:W237-3E")
      (libsource (lib "eagle-import") (part "W237-3E"))
    )
  )
  (nets
    (net (code "1") (name "+6.3FIL") (class "Default")
      (node (ref "R41") (pin "P$2") (pinfunction "2_P$2") (pintype "passive"))
      (node (ref "V1") (pin "4") (pinfunction "H1_4") (pintype "passive"))
    )
    (net (code "2") (name "+LV") (class "Default")
      (node (ref "A1") (pin "1") (pinfunction "IN_1") (pintype "bidirectional"))
      (node (ref "B1") (pin "+") (pinfunction "+_+") (pintype "passive"))
      (node (ref "C19") (pin "1") (pinfunction "1_1") (pintype "passive"))
      (node (ref "C21") (pin "1") (pinfunction "+_1") (pintype "passive"))
      (node (ref "D5") (pin "C") (pinfunction "C_C") (pintype "passive"))
      (node (ref "IC3") (pin "3") (pinfunction "IN_3") (pintype "input"))
    )
    (net (code "3") (name "AC_1") (class "Default")
      (node (ref "B1") (pin "AC1") (pinfunction "AC2_AC1") (pintype "passive"))
      (node (ref "D3") (pin "A") (pinfunction "A_A") (pintype "passive"))
      (node (ref "X2") (pin "2") (pinfunction "KL_2") (pintype "passive"))
    )
    (net (code "4") (name "AC_2") (class "Default")
      (node (ref "B1") (pin "AC2") (pinfunction "AC1_AC2") (pintype "passive"))
      (node (ref "C20") (pin "2") (pinfunction "-_2") (pintype "passive"))
      (node (ref "X2") (pin "1") (pinfunction "KL_1") (pintype "passive"))
    )
    (net (code "5") (name "FB_L") (class "Default")
      (node (ref "C5") (pin "1") (pinfunction "+_1") (pintype "passive"))
      (node (ref "C8") (pin "+") (pinfunction "+_+") (pintype "passive"))
      (node (ref "C9") (pin "+") (pinfunction "+_+") (pintype "passive"))
      (node (ref "D1") (pin "C") (pinfunction "C_C") (pintype "passive"))
      (node (ref "R1") (pin "P$2") (pinfunction "2_P$2") (pintype "passive"))
      (node (ref "R18") (pin "P$1") (pinfunction "1_P$1") (pintype "passive"))
      (node (ref "R19") (pin "P$2") (pinfunction "2_P$2") (pintype "passive"))
    )
    (net (code "6") (name "FB_R") (class "Default")
      (node (ref "C14") (pin "1") (pinfunction "+_1") (pintype "passive"))
      (node (ref "C17") (pin "+") (pinfunction "+_+") (pintype "passive"))
      (node (ref "C18") (pin "+") (pinfunction "+_+") (pintype "passive"))
      (node (ref "D2") (pin "C") (pinfunction "C_C") (pintype "passive"))
      (node (ref "R21") (pin "P$2") (pinfunction "2_P$2") (pintype "passive"))
      (node (ref "R38") (pin "P$1") (pinfunction "1_P$1") (pintype "passive"))
      (node (ref "R39") (pin "P$2") (pinfunction "2_P$2") (pintype "passive"))
    )
    (net (code "7") (name "FGND") (class "Default")
      (node (ref "GB1") (pin "2") (pinfunction "2_2") (pintype "passive"))
      (node (ref "V1") (pin "5") (pinfunction "H3_5") (pintype "passive"))
    )
    (net (code "8") (name "GND") (class "Default")
      (node (ref "A1") (pin "2") (pinfunction "GND_2") (pintype "bidirectional"))
      (node (ref "B1") (pin "-") (pinfunction "-_-") (pintype "passive"))
      (node (ref "C1") (pin "1") (pinfunction "1_1") (pintype "passive"))
      (node (ref "C10") (pin "1") (pinfunction "1_1") (pintype "passive"))
      (node (ref "C12") (pin "1") (pinfunction "1_1") (pintype "passive"))
      (node (ref "C15") (pin "-") (pinfunction "-_-") (pintype "passive"))
      (node (ref "C16") (pin "-") (pinfunction "-_-") (pintype "passive"))
      (node (ref "C19") (pin "2") (pinfunction "2_2") (pintype "passive"))
      (node (ref "C2") (pin "1") (pinfunction "1_1") (pintype "passive"))
      (node (ref "C21") (pin "2") (pinfunction "-_2") (pintype "passive"))
      (node (ref "C22") (pin "2") (pinfunction "2_2") (pintype "passive"))
      (node (ref "C23") (pin "2") (pinfunction "-_2") (pintype "passive"))
      (node (ref "C24") (pin "2") (pinfunction "-_2") (pintype "passive"))
      (node (ref "C25") (pin "2") (pinfunction "-_2") (pintype "passive"))
      (node (ref "C26") (pin "2") (pinfunction "2_2") (pintype "passive"))
      (node (ref "C27") (pin "2") (pinfunction "2_2") (pintype "passive"))
      (node (ref "C28") (pin "-") (pinfunction "-_-") (pintype "passive"))
      (node (ref "C29") (pin "-") (pinfunction "-_-") (pintype "passive"))
      (node (ref "C30") (pin "2") (pinfunction "-_2") (pintype "passive"))
      (node (ref "C31") (pin "2") (pinfunction "2_2") (pintype "passive"))
      (node (ref "C32") (pin "-") (pinfunction "-_-") (pintype "passive"))
      (node (ref "C33") (pin "2") (pinfunction "-_2") (pintype "passive"))
      (node (ref "C6") (pin "-") (pinfunction "-_-") (pintype "passive"))
      (node (ref "C7") (pin "-") (pinfunction "-_-") (pintype "passive"))
      (node (ref "D8") (pin "K") (pinfunction "C_K") (pintype "passive"))
      (node (ref "GB1") (pin "1") (pinfunction "1_1") (pintype "passive"))
      (node (ref "H1") (pin "B3,2") (pinfunction "MOUNT_B3,2") (pintype "passive"))
      (node (ref "IC1") (pin "4") (pinfunction "V-_4") (pintype "power_in"))
      (node (ref "IC2") (pin "4") (pinfunction "V-_4") (pintype "power_in"))
      (node (ref "J1") (pin "S") (pinfunction "SLEEVE_S") (pintype "bidirectional"))
      (node (ref "K1") (pin "2") (pinfunction "O_2") (pintype "passive"))
      (node (ref "K1") (pin "7") (pinfunction "O_7") (pintype "passive"))
      (node (ref "Q10") (pin "1") (pinfunction "E_1") (pintype "passive"))
      (node (ref "Q20") (pin "1") (pinfunction "E_1") (pintype "passive"))
      (node (ref "Q23") (pin "3") (pinfunction "E_3") (pintype "passive"))
      (node (ref "R12") (pin "P$1") (pinfunction "1_P$1") (pintype "passive"))
      (node (ref "R17") (pin "P$1") (pinfunction "1_P$1") (pintype "passive"))
      (node (ref "R20") (pin "P$1") (pinfunction "1_P$1") (pintype "passive"))
      (node (ref "R23") (pin "P$2") (pinfunction "2_P$2") (pintype "passive"))
      (node (ref "R24") (pin "P$1") (pinfunction "1_P$1") (pintype "passive"))
      (node (ref "R27") (pin "P$1") (pinfunction "1_P$1") (pintype "passive"))
      (node (ref "R29") (pin "P$1") (pinfunction "1_P$1") (pintype "passive"))
      (node (ref "R3") (pin "P$2") (pinfunction "2_P$2") (pintype "passive"))
      (node (ref "R32") (pin "P$1") (pinfunction "1_P$1") (pintype "passive"))
      (node (ref "R37") (pin "P$1") (pinfunction "1_P$1") (pintype "passive"))
      (node (ref "R4") (pin "P$1") (pinfunction "1_P$1") (pintype "passive"))
      (node (ref "R40") (pin "P$1") (pinfunction "1_P$1") (pintype "passive"))
      (node (ref "R44") (pin "P$2") (pinfunction "2_P$2") (pintype "passive"))
      (node (ref "R48") (pin "P$2") (pinfunction "2_P$2") (pintype "passive"))
      (node (ref "R50") (pin "P$2") (pinfunction "2_P$2") (pintype "passive"))
      (node (ref "R7") (pin "P$1") (pinfunction "1_P$1") (pintype "passive"))
      (node (ref "R9") (pin "P$1") (pinfunction "1_P$1") (pintype "passive"))
      (node (ref "U1") (pin "4") (pinfunction "GND_4") (pintype "passive"))
      (node (ref "VR1") (pin "1.1.1") (pinfunction "A_1.1.1") (pintype "passive"))
      (node (ref "VR1") (pin "1.1.2") (pinfunction "A_1.1.2") (pintype "passive"))
      (node (ref "VR1") (pin "2.1.1") (pinfunction "A_2.1.1") (pintype "passive"))
      (node (ref "VR1") (pin "2.1.2") (pinfunction "A_2.1.2") (pintype "passive"))
      (node (ref "X1") (pin "2") (pinfunction "KL_2") (pintype "passive"))
    )
    (net (code "9") (name "HT") (class "Default")
      (node (ref "C15") (pin "+") (pinfunction "+_+") (pintype "passive"))
      (node (ref "C32") (pin "+") (pinfunction "+_+") (pintype "passive"))
      (node (ref "C6") (pin "+") (pinfunction "+_+") (pintype "passive"))
      (node (ref "D7") (pin "A") (pinfunction "A_A") (pintype "passive"))
      (node (ref "D9") (pin "C") (pinfunction "C_C") (pintype "passive"))
      (node (ref "IC4") (pin "2") (pinfunction "OUT_2") (pintype "passive"))
      (node (ref "R11") (pin "P$2") (pinfunction "2_P$2") (pintype "passive"))
      (node (ref "R26") (pin "P$2") (pinfunction "2_P$2") (pintype "passive"))
      (node (ref "R28") (pin "P$2") (pinfunction "2_P$2") (pintype "passive"))
      (node (ref "R31") (pin "P$2") (pinfunction "2_P$2") (pintype "passive"))
      (node (ref "R47") (pin "P$1") (pinfunction "1_P$1") (pintype "passive"))
      (node (ref "R6") (pin "P$2") (pinfunction "2_P$2") (pintype "passive"))
      (node (ref "R8") (pin "P$2") (pinfunction "2_P$2") (pintype "passive"))
    )
    (net (code "10") (name "IN_L") (class "Default")
      (node (ref "C4") (pin "1") (pinfunction "1_1") (pintype "passive"))
      (node (ref "VR1") (pin "1.2") (pinfunction "S_1.2") (pintype "passive"))
    )
    (net (code "11") (name "IN_L*") (class "Default")
      (node (ref "VR1") (pin "1.3.1") (pinfunction "E_1.3.1") (pintype "passive"))
      (node (ref "VR1") (pin "1.3.2") (pinfunction "E_1.3.2") (pintype "passive"))
      (node (ref "X1") (pin "1") (pinfunction "KL_1") (pintype "passive"))
    )
    (net (code "12") (name "IN_R") (class "Default")
      (node (ref "C13") (pin "1") (pinfunction "1_1") (pintype "passive"))
      (node (ref "VR1") (pin "2.2.1") (pinfunction "S_2.2.1") (pintype "passive"))
      (node (ref "VR1") (pin "2.2.2") (pinfunction "S_2.2.2") (pintype "passive"))
    )
    (net (code "13") (name "IN_R*") (class "Default")
      (node (ref "VR1") (pin "2.3.1") (pinfunction "E_2.3.1") (pintype "passive"))
      (node (ref "VR1") (pin "2.3.2") (pinfunction "E_2.3.2") (pintype "passive"))
      (node (ref "X1") (pin "3") (pinfunction "KL_3") (pintype "passive"))
    )
    (net (code "14") (name "Net-(A1-OUT)") (class "Default")
      (node (ref "A1") (pin "3") (pinfunction "OUT_3") (pintype "bidirectional"))
      (node (ref "C22") (pin "1") (pinfunction "1_1") (pintype "passive"))
      (node (ref "C24") (pin "1") (pinfunction "+_1") (pintype "passive"))
      (node (ref "R41") (pin "P$1") (pinfunction "1_P$1") (pintype "passive"))
    )
    (net (code "15") (name "Net-(C5--)") (class "Default")
      (node (ref "C5") (pin "2") (pinfunction "-_2") (pintype "passive"))
      (node (ref "D1") (pin "A") (pinfunction "A_A") (pintype "passive"))
      (node (ref "R10") (pin "P$1") (pinfunction "1_P$1") (pintype "passive"))
    )
    (net (code "16") (name "Net-(C14--)") (class "Default")
      (node (ref "C14") (pin "2") (pinfunction "-_2") (pintype "passive"))
      (node (ref "D2") (pin "A") (pinfunction "A_A") (pintype "passive"))
      (node (ref "R30") (pin "P$1") (pinfunction "1_P$1") (pintype "passive"))
    )
    (net (code "17") (name "Net-(C20-+)") (class "Default")
      (node (ref "C20") (pin "1") (pinfunction "+_1") (pintype "passive"))
      (node (ref "D3") (pin "C") (pinfunction "C_C") (pintype "passive"))
      (node (ref "D4") (pin "A") (pinfunction "A_A") (pintype "passive"))
    )
    (net (code "18") (name "Net-(C23-+)") (class "Default")
      (node (ref "C23") (pin "1") (pinfunction "+_1") (pintype "passive"))
      (node (ref "D4") (pin "C") (pinfunction "C_C") (pintype "passive"))
      (node (ref "D7") (pin "C") (pinfunction "C_C") (pintype "passive"))
      (node (ref "Q21") (pin "3") (pinfunction "C_3") (pintype "passive"))
      (node (ref "Q22") (pin "3") (pinfunction "C_3") (pintype "passive"))
      (node (ref "R42") (pin "P$1") (pinfunction "1_P$1") (pintype "passive"))
    )
    (net (code "19") (name "Net-(C25-+)") (class "Default")
      (node (ref "C25") (pin "1") (pinfunction "+_1") (pintype "passive"))
      (node (ref "C27") (pin "1") (pinfunction "1_1") (pintype "passive"))
      (node (ref "D6") (pin "A") (pinfunction "A_A") (pintype "passive"))
      (node (ref "IC3") (pin "1") (pinfunction "ADJ_1") (pintype "input"))
      (node (ref "R43") (pin "P$2") (pinfunction "2_P$2") (pintype "passive"))
      (node (ref "R44") (pin "P$1") (pinfunction "1_P$1") (pintype "passive"))
    )
    (net (code "20") (name "Net-(C30-+)") (class "Default")
      (node (ref "C30") (pin "1") (pinfunction "+_1") (pintype "passive"))
      (node (ref "C31") (pin "1") (pinfunction "1_1") (pintype "passive"))
      (node (ref "D9") (pin "A") (pinfunction "A_A") (pintype "passive"))
      (node (ref "IC4") (pin "1") (pinfunction "ADJ_1") (pintype "input"))
      (node (ref "R47") (pin "P$2") (pinfunction "2_P$2") (pintype "passive"))
      (node (ref "R48") (pin "P$1") (pinfunction "1_P$1") (pintype "passive"))
    )
    (net (code "21") (name "Net-(C33-+)") (class "Default")
      (node (ref "C33") (pin "1") (pinfunction "+_1") (pintype "passive"))
      (node (ref "U1") (pin "1") (pinfunction "CT_1") (pintype "input"))
    )
    (net (code "22") (name "Net-(IC1-+IN)") (class "Default")
      (node (ref "C1") (pin "2") (pinfunction "2_2") (pintype "passive"))
      (node (ref "IC1") (pin "3") (pinfunction "+IN_3") (pintype "input"))
      (node (ref "R1") (pin "P$1") (pinfunction "1_P$1") (pintype "passive"))
    )
    (net (code "23") (name "Net-(IC1--IN)") (class "Default")
      (node (ref "C3") (pin "2") (pinfunction "2_2") (pintype "passive"))
      (node (ref "IC1") (pin "2") (pinfunction "-IN_2") (pintype "input"))
      (node (ref "R2") (pin "P$1") (pinfunction "1_P$1") (pintype "passive"))
      (node (ref "R3") (pin "P$1") (pinfunction "1_P$1") (pintype "passive"))
    )
    (net (code "24") (name "Net-(IC1-OUT)") (class "Default")
      (node (ref "C3") (pin "1") (pinfunction "1_1") (pintype "passive"))
      (node (ref "IC1") (pin "6") (pinfunction "OUT_6") (pintype "output"))
      (node (ref "Q1") (pin "2") (pinfunction "B_2") (pintype "passive"))
    )
    (net (code "25") (name "Net-(IC2-+IN)") (class "Default")
      (node (ref "C10") (pin "2") (pinfunction "2_2") (pintype "passive"))
      (node (ref "IC2") (pin "3") (pinfunction "+IN_3") (pintype "input"))
      (node (ref "R21") (pin "P$1") (pinfunction "1_P$1") (pintype "passive"))
    )
    (net (code "26") (name "Net-(IC2--IN)") (class "Default")
      (node (ref "C11") (pin "2") (pinfunction "2_2") (pintype "passive"))
      (node (ref "IC2") (pin "2") (pinfunction "-IN_2") (pintype "input"))
      (node (ref "R22") (pin "P$1") (pinfunction "1_P$1") (pintype "passive"))
      (node (ref "R23") (pin "P$1") (pinfunction "1_P$1") (pintype "passive"))
    )
    (net (code "27") (name "Net-(IC2-OUT)") (class "Default")
      (node (ref "C11") (pin "1") (pinfunction "1_1") (pintype "passive"))
      (node (ref "IC2") (pin "6") (pinfunction "OUT_6") (pintype "output"))
      (node (ref "Q11") (pin "2") (pinfunction "B_2") (pintype "passive"))
    )
    (net (code "28") (name "Net-(IC4-IN)") (class "Default")
      (node (ref "IC4") (pin "3") (pinfunction "IN_3") (pintype "input"))
      (node (ref "Q22") (pin "1") (pinfunction "E_1") (pintype "passive"))
      (node (ref "R45") (pin "P$1") (pinfunction "1_P$1") (pintype "passive"))
    )
    (net (code "29") (name "Net-(K1A-2)") (class "Default")
      (node (ref "D10") (pin "A") (pinfunction "A_A") (pintype "passive"))
      (node (ref "K1") (pin "8") (pinfunction "2_8") (pintype "passive"))
      (node (ref "R52") (pin "P$1") (pinfunction "1_P$1") (pintype "passive"))
    )
    (net (code "30") (name "Net-(Q1-C)") (class "Default")
      (node (ref "Q1") (pin "3") (pinfunction "C_3") (pintype "passive"))
      (node (ref "Q2") (pin "1") (pinfunction "C_1") (pintype "passive"))
      (node (ref "Q4") (pin "2") (pinfunction "B_2") (pintype "passive"))
    )
    (net (code "31") (name "Net-(Q1-E)") (class "Default")
      (node (ref "Q1") (pin "1") (pinfunction "E_1") (pintype "passive"))
      (node (ref "R7") (pin "P$2") (pinfunction "2_P$2") (pintype "passive"))
    )
    (net (code "32") (name "Net-(Q2-B)") (class "Default")
      (node (ref "Q2") (pin "2") (pinfunction "B_2") (pintype "passive"))
      (node (ref "Q3") (pin "1") (pinfunction "C_1") (pintype "passive"))
      (node (ref "Q3") (pin "2") (pinfunction "B_2") (pintype "passive"))
      (node (ref "Q4") (pin "3") (pinfunction "E_3") (pintype "passive"))
    )
    (net (code "33") (name "Net-(Q2-E)") (class "Default")
      (node (ref "Q2") (pin "3") (pinfunction "E_3") (pintype "passive"))
      (node (ref "R6") (pin "P$1") (pinfunction "1_P$1") (pintype "passive"))
    )
    (net (code "34") (name "Net-(Q3-E)") (class "Default")
      (node (ref "Q3") (pin "3") (pinfunction "E_3") (pintype "passive"))
      (node (ref "R8") (pin "P$1") (pinfunction "1_P$1") (pintype "passive"))
    )
    (net (code "35") (name "Net-(Q4-C)") (class "Default")
      (node (ref "Q4") (pin "1") (pinfunction "C_1") (pintype "passive"))
      (node (ref "Q5") (pin "2") (pinfunction "B_2") (pintype "passive"))
      (node (ref "V1") (pin "1") (pinfunction "TA_1") (pintype "passive"))
    )
    (net (code "36") (name "Net-(Q5-C)") (class "Default")
      (node (ref "Q5") (pin "1") (pinfunction "C_1") (pintype "passive"))
      (node (ref "Q6") (pin "1") (pinfunction "C_1") (pintype "passive"))
      (node (ref "Q7") (pin "2") (pinfunction "B_2") (pintype "passive"))
      (node (ref "R13") (pin "P$2") (pinfunction "2_P$2") (pintype "passive"))
    )
    (net (code "37") (name "Net-(Q5-E)") (class "Default")
      (node (ref "Q5") (pin "3") (pinfunction "E_3") (pintype "passive"))
      (node (ref "R11") (pin "P$1") (pinfunction "1_P$1") (pintype "passive"))
    )
    (net (code "38") (name "Net-(Q6-B)") (class "Default")
      (node (ref "Q6") (pin "2") (pinfunction "B_2") (pintype "passive"))
      (node (ref "R13") (pin "P$1") (pinfunction "1_P$1") (pintype "passive"))
      (node (ref "R14") (pin "P$1") (pinfunction "1_P$1") (pintype "passive"))
    )
    (net (code "39") (name "Net-(Q6-E)") (class "Default")
      (node (ref "Q6") (pin "3") (pinfunction "E_3") (pintype "passive"))
      (node (ref "Q8") (pin "2") (pinfunction "B_2") (pintype "passive"))
      (node (ref "R12") (pin "P$2") (pinfunction "2_P$2") (pintype "passive"))
      (node (ref "R15") (pin "1") (pinfunction "CCW_1") (pintype "passive"))
      (node (ref "R15") (pin "2") (pinfunction "WIPER_2") (pintype "passive"))
    )
    (net (code "40") (name "Net-(Q7-C)") (class "Default")
      (node (ref "Q7") (pin "1") (pinfunction "C_1") (pintype "passive"))
      (node (ref "Q9") (pin "3") (pinfunction "B_3") (pintype "passive"))
      (node (ref "R16") (pin "P$1") (pinfunction "1_P$1") (pintype "passive"))
    )
    (net (code "41") (name "Net-(Q7-E)") (class "Default")
      (node (ref "Q7") (pin "3") (pinfunction "E_3") (pintype "passive"))
      (node (ref "Q9") (pin "2") (pinfunction "C_2") (pintype "passive"))
      (node (ref "R18") (pin "P$2") (pinfunction "2_P$2") (pintype "passive"))
    )
    (net (code "42") (name "Net-(Q10-B)") (class "Default")
      (node (ref "Q10") (pin "3") (pinfunction "B_3") (pintype "passive"))
      (node (ref "Q8") (pin "1") (pinfunction "C_1") (pintype "passive"))
      (node (ref "R17") (pin "P$2") (pinfunction "2_P$2") (pintype "passive"))
    )
    (net (code "43") (name "Net-(Q10-C)") (class "Default")
      (node (ref "Q10") (pin "2") (pinfunction "C_2") (pintype "passive"))
      (node (ref "Q8") (pin "3") (pinfunction "E_3") (pintype "passive"))
      (node (ref "R19") (pin "P$1") (pinfunction "1_P$1") (pintype "passive"))
    )
    (net (code "44") (name "Net-(Q11-C)") (class "Default")
      (node (ref "Q11") (pin "3") (pinfunction "C_3") (pintype "passive"))
      (node (ref "Q12") (pin "1") (pinfunction "C_1") (pintype "passive"))
      (node (ref "Q14") (pin "2") (pinfunction "B_2") (pintype "passive"))
    )
    (net (code "45") (name "Net-(Q11-E)") (class "Default")
      (node (ref "Q11") (pin "1") (pinfunction "E_1") (pintype "passive"))
      (node (ref "R27") (pin "P$2") (pinfunction "2_P$2") (pintype "passive"))
    )
    (net (code "46") (name "Net-(Q12-B)") (class "Default")
      (node (ref "Q12") (pin "2") (pinfunction "B_2") (pintype "passive"))
      (node (ref "Q13") (pin "1") (pinfunction "C_1") (pintype "passive"))
      (node (ref "Q13") (pin "2") (pinfunction "B_2") (pintype "passive"))
      (node (ref "Q14") (pin "3") (pinfunction "E_3") (pintype "passive"))
    )
    (net (code "47") (name "Net-(Q12-E)") (class "Default")
      (node (ref "Q12") (pin "3") (pinfunction "E_3") (pintype "passive"))
      (node (ref "R26") (pin "P$1") (pinfunction "1_P$1") (pintype "passive"))
    )
    (net (code "48") (name "Net-(Q13-E)") (class "Default")
      (node (ref "Q13") (pin "3") (pinfunction "E_3") (pintype "passive"))
      (node (ref "R28") (pin "P$1") (pinfunction "1_P$1") (pintype "passive"))
    )
    (net (code "49") (name "Net-(Q14-C)") (class "Default")
      (node (ref "Q14") (pin "1") (pinfunction "C_1") (pintype "passive"))
      (node (ref "Q15") (pin "2") (pinfunction "B_2") (pintype "passive"))
      (node (ref "V1") (pin "6") (pinfunction "TA_6") (pintype "passive"))
    )
    (net (code "50") (name "Net-(Q15-C)") (class "Default")
      (node (ref "Q15") (pin "1") (pinfunction "C_1") (pintype "passive"))
      (node (ref "Q16") (pin "1") (pinfunction "C_1") (pintype "passive"))
      (node (ref "Q17") (pin "2") (pinfunction "B_2") (pintype "passive"))
      (node (ref "R33") (pin "P$2") (pinfunction "2_P$2") (pintype "passive"))
    )
    (net (code "51") (name "Net-(Q15-E)") (class "Default")
      (node (ref "Q15") (pin "3") (pinfunction "E_3") (pintype "passive"))
      (node (ref "R31") (pin "P$1") (pinfunction "1_P$1") (pintype "passive"))
    )
    (net (code "52") (name "Net-(Q16-B)") (class "Default")
      (node (ref "Q16") (pin "2") (pinfunction "B_2") (pintype "passive"))
      (node (ref "R33") (pin "P$1") (pinfunction "1_P$1") (pintype "passive"))
      (node (ref "R34") (pin "P$1") (pinfunction "1_P$1") (pintype "passive"))
    )
    (net (code "53") (name "Net-(Q16-E)") (class "Default")
      (node (ref "Q16") (pin "3") (pinfunction "E_3") (pintype "passive"))
      (node (ref "Q18") (pin "2") (pinfunction "B_2") (pintype "passive"))
      (node (ref "R32") (pin "P$2") (pinfunction "2_P$2") (pintype "passive"))
      (node (ref "R35") (pin "1") (pinfunction "CCW_1") (pintype "passive"))
      (node (ref "R35") (pin "2") (pinfunction "WIPER_2") (pintype "passive"))
    )
    (net (code "54") (name "Net-(Q17-C)") (class "Default")
      (node (ref "Q17") (pin "1") (pinfunction "C_1") (pintype "passive"))
      (node (ref "Q19") (pin "3") (pinfunction "B_3") (pintype "passive"))
      (node (ref "R36") (pin "P$1") (pinfunction "1_P$1") (pintype "passive"))
    )
    (net (code "55") (name "Net-(Q17-E)") (class "Default")
      (node (ref "Q17") (pin "3") (pinfunction "E_3") (pintype "passive"))
      (node (ref "Q19") (pin "2") (pinfunction "C_2") (pintype "passive"))
      (node (ref "R38") (pin "P$2") (pinfunction "2_P$2") (pintype "passive"))
    )
    (net (code "56") (name "Net-(Q18-C)") (class "Default")
      (node (ref "Q18") (pin "1") (pinfunction "C_1") (pintype "passive"))
      (node (ref "Q20") (pin "3") (pinfunction "B_3") (pintype "passive"))
      (node (ref "R37") (pin "P$2") (pinfunction "2_P$2") (pintype "passive"))
    )
    (net (code "57") (name "Net-(Q18-E)") (class "Default")
      (node (ref "Q18") (pin "3") (pinfunction "E_3") (pintype "passive"))
      (node (ref "Q20") (pin "2") (pinfunction "C_2") (pintype "passive"))
      (node (ref "R39") (pin "P$1") (pinfunction "1_P$1") (pintype "passive"))
    )
    (net (code "58") (name "Net-(Q21-B)") (class "Default")
      (node (ref "C26") (pin "1") (pinfunction "1_1") (pintype "passive"))
      (node (ref "C28") (pin "+") (pinfunction "+_+") (pintype "passive"))
      (node (ref "Q21") (pin "2") (pinfunction "B_2") (pintype "passive"))
      (node (ref "R42") (pin "P$2") (pinfunction "2_P$2") (pintype "passive"))
    )
    (net (code "59") (name "Net-(Q21-E)") (class "Default")
      (node (ref "Q21") (pin "1") (pinfunction "E_1") (pintype "passive"))
      (node (ref "Q22") (pin "2") (pinfunction "B_2") (pintype "passive"))
      (node (ref "R45") (pin "P$2") (pinfunction "2_P$2") (pintype "passive"))
    )
    (net (code "60") (name "Net-(Q23-B)") (class "Default")
      (node (ref "Q23") (pin "2") (pinfunction "B_2") (pintype "passive"))
      (node (ref "R51") (pin "P$2") (pinfunction "2_P$2") (pintype "passive"))
      (node (ref "U1") (pin "8") (pinfunction "~{RESET}_8") (pintype "output"))
    )
    (net (code "61") (name "Net-(Q23-C)") (class "Default")
      (node (ref "Q23") (pin "1") (pinfunction "C_1") (pintype "passive"))
      (node (ref "R52") (pin "P$2") (pinfunction "2_P$2") (pintype "passive"))
    )
    (net (code "62") (name "Net-(R4-2)") (class "Default")
      (node (ref "C4") (pin "2") (pinfunction "2_2") (pintype "passive"))
      (node (ref "R4") (pin "P$2") (pinfunction "2_P$2") (pintype "passive"))
      (node (ref "R5") (pin "P$2") (pinfunction "2_P$2") (pintype "passive"))
    )
    (net (code "63") (name "Net-(R5-1)") (class "Default")
      (node (ref "R5") (pin "P$1") (pinfunction "1_P$1") (pintype "passive"))
      (node (ref "V1") (pin "2") (pinfunction "TG_2") (pintype "passive"))
    )
    (net (code "64") (name "Net-(R10-2)") (class "Default")
      (node (ref "R10") (pin "P$2") (pinfunction "2_P$2") (pintype "passive"))
      (node (ref "R9") (pin "P$2") (pinfunction "2_P$2") (pintype "passive"))
      (node (ref "V1") (pin "3") (pinfunction "TK_3") (pintype "passive"))
    )
    (net (code "65") (name "Net-(R14-2)") (class "Default")
      (node (ref "R14") (pin "P$2") (pinfunction "2_P$2") (pintype "passive"))
      (node (ref "R15") (pin "3") (pinfunction "CW_3") (pintype "passive"))
    )
    (net (code "66") (name "Net-(R24-2)") (class "Default")
      (node (ref "C13") (pin "2") (pinfunction "2_2") (pintype "passive"))
      (node (ref "R24") (pin "P$2") (pinfunction "2_P$2") (pintype "passive"))
      (node (ref "R25") (pin "P$2") (pinfunction "2_P$2") (pintype "passive"))
    )
    (net (code "67") (name "Net-(R25-1)") (class "Default")
      (node (ref "R25") (pin "P$1") (pinfunction "1_P$1") (pintype "passive"))
      (node (ref "V1") (pin "7") (pinfunction "TG_7") (pintype "passive"))
    )
    (net (code "68") (name "Net-(R29-2)") (class "Default")
      (node (ref "R29") (pin "P$2") (pinfunction "2_P$2") (pintype "passive"))
      (node (ref "R30") (pin "P$2") (pinfunction "2_P$2") (pintype "passive"))
      (node (ref "V1") (pin "8") (pinfunction "TK_8") (pintype "passive"))
    )
    (net (code "69") (name "Net-(R34-2)") (class "Default")
      (node (ref "R34") (pin "P$2") (pinfunction "2_P$2") (pintype "passive"))
      (node (ref "R35") (pin "3") (pinfunction "CW_3") (pintype "passive"))
    )
    (net (code "70") (name "Net-(R46-2)") (class "Default")
      (node (ref "D8") (pin "A") (pinfunction "A_A") (pintype "passive"))
      (node (ref "R46") (pin "P$2") (pinfunction "2_P$2") (pintype "passive"))
    )
    (net (code "71") (name "Net-(R49-2)") (class "Default")
      (node (ref "R49") (pin "P$2") (pinfunction "2_P$2") (pintype "passive"))
      (node (ref "R50") (pin "P$1") (pinfunction "1_P$1") (pintype "passive"))
      (node (ref "U1") (pin "2") (pinfunction "SENSE_2") (pintype "input"))
    )
    (net (code "72") (name "OUT_L") (class "Default")
      (node (ref "C8") (pin "-") (pinfunction "-_-") (pintype "passive"))
      (node (ref "C9") (pin "-") (pinfunction "-_-") (pintype "passive"))
      (node (ref "K1") (pin "4") (pinfunction "S_4") (pintype "passive"))
      (node (ref "R20") (pin "P$2") (pinfunction "2_P$2") (pintype "passive"))
    )
    (net (code "73") (name "OUT_L*") (class "Default")
      (node (ref "J1") (pin "T") (pinfunction "LEFT_T") (pintype "bidirectional"))
      (node (ref "K1") (pin "3") (pinfunction "P_3") (pintype "passive"))
    )
    (net (code "74") (name "OUT_R") (class "Default")
      (node (ref "C17") (pin "-") (pinfunction "-_-") (pintype "passive"))
      (node (ref "C18") (pin "-") (pinfunction "-_-") (pintype "passive"))
      (node (ref "K1") (pin "5") (pinfunction "S_5") (pintype "passive"))
      (node (ref "R40") (pin "P$2") (pinfunction "2_P$2") (pintype "passive"))
    )
    (net (code "75") (name "OUT_R*") (class "Default")
      (node (ref "J1") (pin "R") (pinfunction "RIGHT_R") (pintype "bidirectional"))
      (node (ref "K1") (pin "6") (pinfunction "P_6") (pintype "passive"))
    )
    (net (code "76") (name "VCC") (class "Default")
      (node (ref "C12") (pin "2") (pinfunction "2_2") (pintype "passive"))
      (node (ref "C16") (pin "+") (pinfunction "+_+") (pintype "passive"))
      (node (ref "C2") (pin "2") (pinfunction "2_2") (pintype "passive"))
      (node (ref "C29") (pin "+") (pinfunction "+_+") (pintype "passive"))
      (node (ref "C7") (pin "+") (pinfunction "+_+") (pintype "passive"))
      (node (ref "D10") (pin "C") (pinfunction "C_C") (pintype "passive"))
      (node (ref "D5") (pin "A") (pinfunction "A_A") (pintype "passive"))
      (node (ref "D6") (pin "C") (pinfunction "C_C") (pintype "passive"))
      (node (ref "IC1") (pin "7") (pinfunction "V+_7") (pintype "power_in"))
      (node (ref "IC2") (pin "7") (pinfunction "V+_7") (pintype "power_in"))
      (node (ref "IC3") (pin "2") (pinfunction "OUT_2") (pintype "passive"))
      (node (ref "K1") (pin "1") (pinfunction "1_1") (pintype "passive"))
      (node (ref "Q19") (pin "1") (pinfunction "E_1") (pintype "passive"))
      (node (ref "Q9") (pin "1") (pinfunction "E_1") (pintype "passive"))
      (node (ref "R16") (pin "P$2") (pinfunction "2_P$2") (pintype "passive"))
      (node (ref "R2") (pin "P$2") (pinfunction "2_P$2") (pintype "passive"))
      (node (ref "R22") (pin "P$2") (pinfunction "2_P$2") (pintype "passive"))
      (node (ref "R36") (pin "P$2") (pinfunction "2_P$2") (pintype "passive"))
      (node (ref "R43") (pin "P$1") (pinfunction "1_P$1") (pintype "passive"))
      (node (ref "R46") (pin "P$1") (pinfunction "1_P$1") (pintype "passive"))
      (node (ref "R49") (pin "P$1") (pinfunction "1_P$1") (pintype "passive"))
      (node (ref "R51") (pin "P$1") (pinfunction "1_P$1") (pintype "passive"))
      (node (ref "U1") (pin "5") (pinfunction "VCC_5") (pintype "power_in"))
    )
    (net (code "77") (name "unconnected-(IC1-ON1-Pad1)") (class "Default")
      (node (ref "IC1") (pin "1") (pinfunction "ON1_1") (pintype "passive"))
    )
    (net (code "78") (name "unconnected-(IC1-ON2-Pad5)") (class "Default")
      (node (ref "IC1") (pin "5") (pinfunction "ON2_5") (pintype "passive"))
    )
    (net (code "79") (name "unconnected-(IC1-OPT-Pad8)") (class "Default")
      (node (ref "IC1") (pin "8") (pinfunction "OPT_8") (pintype "passive"))
    )
    (net (code "80") (name "unconnected-(IC2-ON1-Pad1)") (class "Default")
      (node (ref "IC2") (pin "1") (pinfunction "ON1_1") (pintype "passive"))
    )
    (net (code "81") (name "unconnected-(IC2-ON2-Pad5)") (class "Default")
      (node (ref "IC2") (pin "5") (pinfunction "ON2_5") (pintype "passive"))
    )
    (net (code "82") (name "unconnected-(IC2-OPT-Pad8)") (class "Default")
      (node (ref "IC2") (pin "8") (pinfunction "OPT_8") (pintype "passive"))
    )
    (net (code "83") (name "unconnected-(U1-NC-Pad3)") (class "Default")
      (node (ref "U1") (pin "3") (pinfunction "NC_3") (pintype "no_connect"))
    )
    (net (code "84") (name "unconnected-(U1-NC_2-Pad6)") (class "Default")
      (node (ref "U1") (pin "6") (pinfunction "NC_2_6") (pintype "no_connect"))
    )
    (net (code "85") (name "unconnected-(U1-NC_3-Pad7)") (class "Default")
      (node (ref "U1") (pin "7") (pinfunction "NC_3_7") (pintype "no_connect"))
    )
    (net (code "86") (name "unconnected-(V1A-H2-Pad9)") (class "Default")
      (node (ref "V1") (pin "9") (pinfunction "H2_9") (pintype "passive"))
    )
  )
)
